# 30_ATMega32u4.net
KiCad netlist of a schematic drawn in Altium Designer
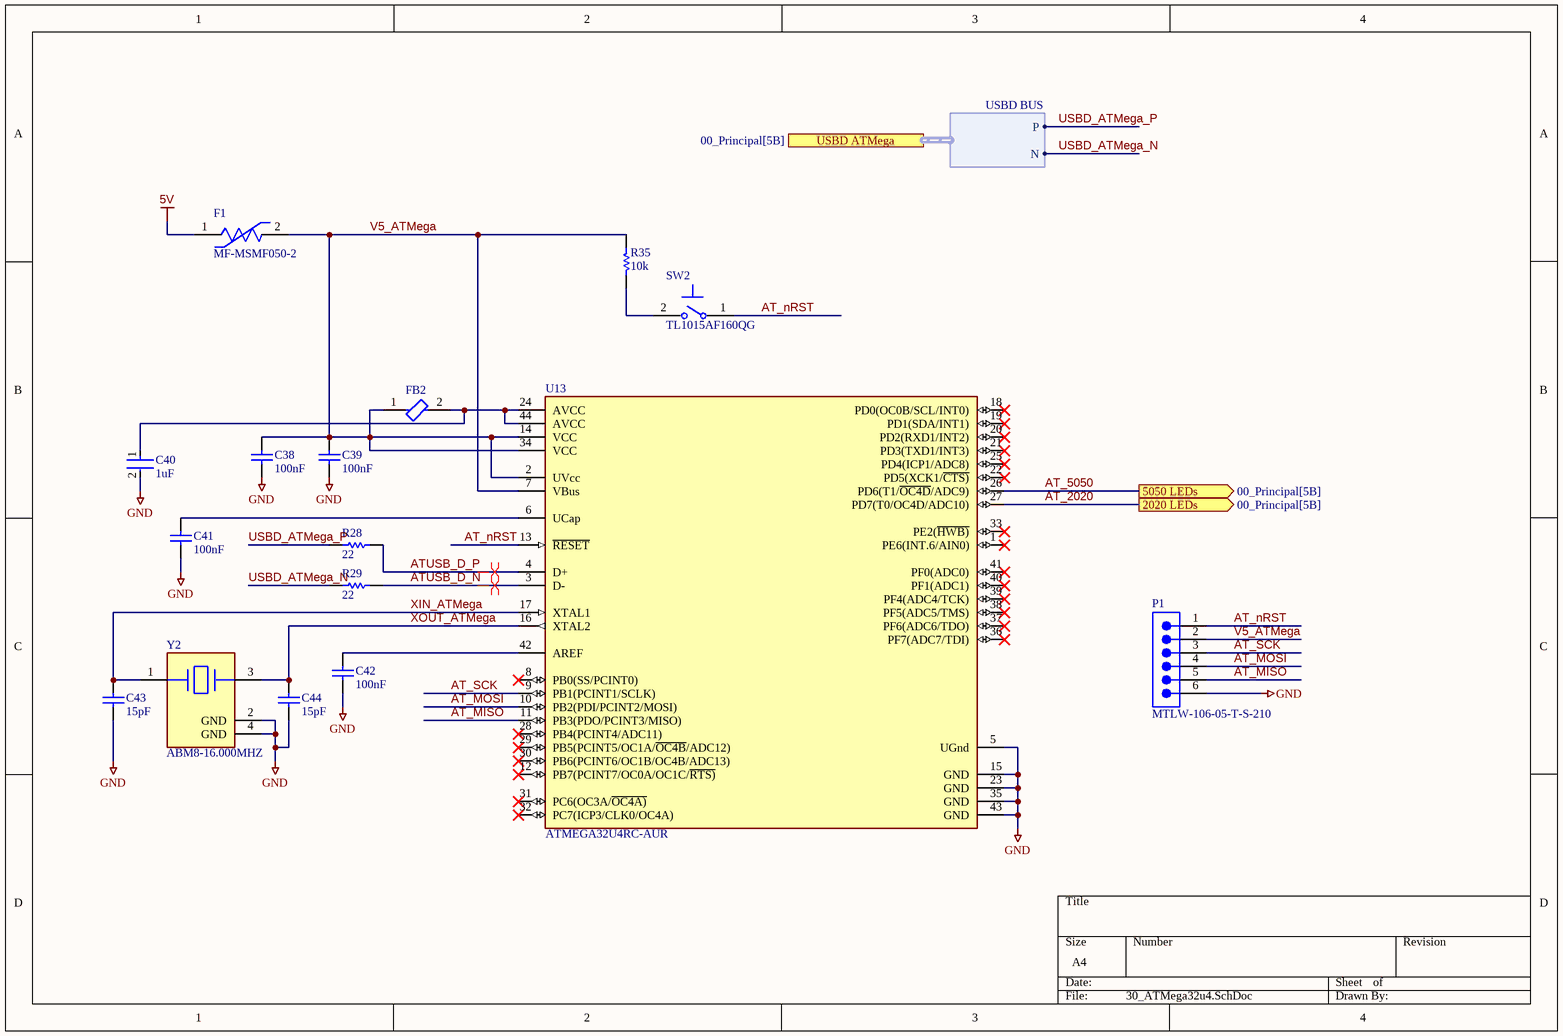
[diagram p0: 30_ATMega32u4.SchDoc]

(export (version "E")
  (design (tool "Eeschema 10.0.6"))
  (components
    (comp (ref "C38")
      (value "100nF")
      (footprint "CAPC1005X55X25NL05T05")
      (fields (field (name "MANUFACTURER") "Vitramon") (field (name "PART NUMBER") "VJ0402Y104KXJCW1BC"))
      (libsource (lib "Altium Content Vault") (part "CAP"))
    )
    (comp (ref "C39")
      (value "100nF")
      (footprint "CAPC1005X55X25NL05T05")
      (fields (field (name "MANUFACTURER") "Vitramon") (field (name "PART NUMBER") "VJ0402Y104KXJCW1BC"))
      (libsource (lib "Altium Content Vault") (part "CAP"))
    )
    (comp (ref "C40")
      (value "1uF")
      (footprint "FP-C0402C-BB-IPC_B")
      (description "CAP CER 1UF 16V X5R 0402")
      (fields (field (name "TOLERANCE") "10%"))
      (libsource (lib "Altium Content Vault") (part "b4654b650e69147ec39a6b967a45e02"))
    )
    (comp (ref "C41")
      (value "100nF")
      (footprint "CAPC1005X55X25NL05T05")
      (fields (field (name "MANUFACTURER") "Vitramon") (field (name "PART NUMBER") "VJ0402Y104KXJCW1BC"))
      (libsource (lib "Altium Content Vault") (part "CAP"))
    )
    (comp (ref "C42")
      (value "100nF")
      (footprint "CAPC1005X55X25NL05T05")
      (fields (field (name "MANUFACTURER") "Vitramon") (field (name "PART NUMBER") "VJ0402Y104KXJCW1BC"))
      (libsource (lib "Altium Content Vault") (part "CAP"))
    )
    (comp (ref "C43")
      (value "15pF")
      (footprint "CAPC1005X56X25NL10T15")
      (fields
        (field (name "MANUFACTURER") "AVX Interconnect / Elco")
        (field (name "PART NUMBER") "0402YA150JAT2A")
      )
      (libsource (lib "Altium Content Vault") (part "CAP"))
    )
    (comp (ref "C44")
      (value "15pF")
      (footprint "CAPC1005X56X25NL10T15")
      (fields
        (field (name "MANUFACTURER") "AVX Interconnect / Elco")
        (field (name "PART NUMBER") "0402YA150JAT2A")
      )
      (libsource (lib "Altium Content Vault") (part "CAP"))
    )
    (comp (ref "F1")
      (value "MF-MSMF050-2")
      (footprint "FP-MF-MSMF050-2-MFG")
      (description "PTC RESET FUSE 15V 500MA 1812")
      (fields
        (field (name "MANUFACTURER") "Bourns")
        (field (name "OCTOPART") "https://octopart.com/mf-msmf050-2-bourns-28047")
      )
      (libsource (lib "Altium Content Vault") (part "fc31388045fc42ab786d6d00b506e9f"))
    )
    (comp (ref "FB2")
      (value "MH2029-300Y")
      (footprint "FP-MH2029-MFG")
      (description "FERRITE BEAD 30 OHM 0805 1LN")
      (fields
        (field (name "OCTOPART") "https://octopart.com/mh2029-300y-bourns-756929")
        (field (name "MANUFACTURER") "Bourns")
      )
      (libsource (lib "Altium Content Vault") (part "5f30dd21d616792df468990f7003faa"))
    )
    (comp (ref "P1")
      (value "MTLW-106-05-T-S-210")
      (footprint "SMTC-MTLW-106-05-X-S-210")
      (fields (field (name "MANUFACTURER") "Samtec"))
      (libsource (lib "Altium Content Vault") (part "SMTC-MTLW-106-05-X-S-210"))
    )
    (comp (ref "R28")
      (value "22")
      (footprint "RESC1005X40X25NL05T05")
      (description "Chip Resistor, 22 Ohm, +/- 1%, 0.1 W, -55 to 155 degC, 0402 (1005 Metric), RoHS, Tape and Reel")
      (fields (field (name "PARTNUMBER") "ERJ-2RKF22R0X") (field (name "TOLERANCE") "1%"))
      (libsource (lib "Altium Content Vault") (part "RES-2"))
    )
    (comp (ref "R29")
      (value "22")
      (footprint "RESC1005X40X25NL05T05")
      (description "Chip Resistor, 22 Ohm, +/- 1%, 0.1 W, -55 to 155 degC, 0402 (1005 Metric), RoHS, Tape and Reel")
      (fields (field (name "PARTNUMBER") "ERJ-2RKF22R0X") (field (name "TOLERANCE") "1%"))
      (libsource (lib "Altium Content Vault") (part "RES-2"))
    )
    (comp (ref "R35")
      (value "10k")
      (footprint "RESC1005X40X25NL05T05")
      (fields (field (name "MANUFACTURER") "Panasonic") (field (name "PART NUMBER") "ERJ-2RHD1002X"))
      (libsource (lib "Altium Content Vault") (part "RES"))
    )
    (comp (ref "SW2")
      (value "TL1015AF160QG")
      (footprint "FP-TL1015AF160QG-MFG")
      (description "SWITCH TACTILE SPST-NO 0.05A 12V")
      (libsource (lib "Altium Content Vault") (part "2041f8efb62e6aaa548c9fd35e2c2f1"))
    )
    (comp (ref "U13")
      (value "ATMEGA32U4RC-AUR")
      (footprint "FP-ML-MFG")
      (description "IC MCU 8BIT 32KB FLASH 44TQFP")
      (libsource (lib "Altium Content Vault") (part "d4543ce5d9f9ec65ed1cf9abf6f4f52"))
    )
    (comp (ref "Y2")
      (value "ABM8-16.000MHZ")
      (footprint "FP-ABM8-MFG")
      (description "Crystal 16MHz ±20ppm 18pF SMD-4 3.2mm x 2.5mm")
      (libsource (lib "Altium Content Vault") (part "dfdb7f9a12507849fb681da9a70121c"))
    )
  )
  (nets
    (net (code "3") (name "/ATUSB_D_N") (class "Default")
      (node (ref "R29") (pin "2") (pinfunction "2_2") (pintype "passive"))
      (node (ref "U13") (pin "3") (pinfunction "D-_3") (pintype "passive"))
    )
    (net (code "4") (name "/ATUSB_D_P") (class "Default")
      (node (ref "R28") (pin "2") (pinfunction "2_2") (pintype "passive"))
      (node (ref "U13") (pin "4") (pinfunction "D+_4") (pintype "passive"))
    )
    (net (code "5") (name "/AT_2020") (class "Default")
      (node (ref "U13") (pin "27") (pinfunction "PD7(T0/OC4D/ADC10)_27") (pintype "bidirectional"))
    )
    (net (code "6") (name "/AT_5050") (class "Default")
      (node (ref "U13") (pin "26") (pinfunction "PD6(T1/~{OC4D}/ADC9)_26") (pintype "bidirectional"))
    )
    (net (code "7") (name "/AT_MISO") (class "Default")
      (node (ref "P1") (pin "5") (pinfunction "5_5") (pintype "passive"))
      (node (ref "U13") (pin "11") (pinfunction "PB3(PDO/PCINT3/MISO)_11") (pintype "bidirectional"))
    )
    (net (code "8") (name "/AT_MOSI") (class "Default")
      (node (ref "P1") (pin "4") (pinfunction "4_4") (pintype "passive"))
      (node (ref "U13") (pin "10") (pinfunction "PB2(PDI/PCINT2/MOSI)_10") (pintype "bidirectional"))
    )
    (net (code "9") (name "/AT_SCK") (class "Default")
      (node (ref "P1") (pin "3") (pinfunction "3_3") (pintype "passive"))
      (node (ref "U13") (pin "9") (pinfunction "PB1(PCINT1/SCLK)_9") (pintype "bidirectional"))
    )
    (net (code "10") (name "/AT_nRST") (class "Default")
      (node (ref "P1") (pin "1") (pinfunction "1_1") (pintype "passive"))
      (node (ref "SW2") (pin "1") (pinfunction "1_1") (pintype "passive"))
      (node (ref "U13") (pin "13") (pinfunction "~{RESET}_13") (pintype "input"))
    )
    (net (code "11") (name "/USBD_ATMega_N") (class "Default")
      (node (ref "R29") (pin "1") (pinfunction "1_1") (pintype "passive"))
    )
    (net (code "12") (name "/USBD_ATMega_P") (class "Default")
      (node (ref "R28") (pin "1") (pinfunction "1_1") (pintype "passive"))
    )
    (net (code "13") (name "/V5_ATMega") (class "Default")
      (node (ref "C38") (pin "2") (pinfunction "2_2") (pintype "passive"))
      (node (ref "C39") (pin "2") (pinfunction "2_2") (pintype "passive"))
      (node (ref "F1") (pin "2") (pinfunction "2_2") (pintype "passive"))
      (node (ref "FB2") (pin "1") (pinfunction "1_1") (pintype "passive"))
      (node (ref "P1") (pin "2") (pinfunction "2_2") (pintype "passive"))
      (node (ref "R35") (pin "2") (pinfunction "2_2") (pintype "passive"))
      (node (ref "U13") (pin "14") (pinfunction "VCC_14") (pintype "power_in"))
      (node (ref "U13") (pin "2") (pinfunction "UVcc_2") (pintype "power_in"))
      (node (ref "U13") (pin "34") (pinfunction "VCC_34") (pintype "power_in"))
      (node (ref "U13") (pin "7") (pinfunction "VBus_7") (pintype "power_in"))
    )
    (net (code "14") (name "/XIN_ATMega") (class "Default")
      (node (ref "C43") (pin "2") (pinfunction "2_2") (pintype "passive"))
      (node (ref "U13") (pin "17") (pinfunction "XTAL1_17") (pintype "input"))
      (node (ref "Y2") (pin "1") (pinfunction "1_1") (pintype "passive"))
    )
    (net (code "15") (name "/XOUT_ATMega") (class "Default")
      (node (ref "C44") (pin "2") (pinfunction "2_2") (pintype "passive"))
      (node (ref "U13") (pin "16") (pinfunction "XTAL2_16") (pintype "output"))
      (node (ref "Y2") (pin "3") (pinfunction "3_3") (pintype "passive"))
    )
    (net (code "17") (name "5V") (class "Default")
      (node (ref "F1") (pin "1") (pinfunction "1_1") (pintype "passive"))
    )
    (net (code "18") (name "GND") (class "Default")
      (node (ref "C38") (pin "1") (pinfunction "1_1") (pintype "passive"))
      (node (ref "C39") (pin "1") (pinfunction "1_1") (pintype "passive"))
      (node (ref "C40") (pin "2") (pinfunction "2_2") (pintype "passive"))
      (node (ref "C41") (pin "1") (pinfunction "1_1") (pintype "passive"))
      (node (ref "C42") (pin "1") (pinfunction "1_1") (pintype "passive"))
      (node (ref "C43") (pin "1") (pinfunction "1_1") (pintype "passive"))
      (node (ref "C44") (pin "1") (pinfunction "1_1") (pintype "passive"))
      (node (ref "P1") (pin "6") (pinfunction "6_6") (pintype "passive"))
      (node (ref "U13") (pin "15") (pinfunction "GND_15") (pintype "power_in"))
      (node (ref "U13") (pin "23") (pinfunction "GND_23") (pintype "power_in"))
      (node (ref "U13") (pin "35") (pinfunction "GND_35") (pintype "power_in"))
      (node (ref "U13") (pin "43") (pinfunction "GND_43") (pintype "power_in"))
      (node (ref "U13") (pin "5") (pinfunction "UGnd_5") (pintype "power_in"))
      (node (ref "Y2") (pin "2") (pinfunction "GND_2") (pintype "power_in"))
      (node (ref "Y2") (pin "4") (pinfunction "GND_4") (pintype "power_in"))
    )
    (net (code "19") (name "Net-(C40-Pad1)") (class "Default")
      (node (ref "C40") (pin "1") (pinfunction "1_1") (pintype "passive"))
      (node (ref "FB2") (pin "2") (pinfunction "2_2") (pintype "passive"))
      (node (ref "U13") (pin "24") (pinfunction "AVCC_24") (pintype "power_in"))
      (node (ref "U13") (pin "44") (pinfunction "AVCC_44") (pintype "power_in"))
    )
    (net (code "20") (name "Net-(R35-Pad1)") (class "Default")
      (node (ref "R35") (pin "1") (pinfunction "1_1") (pintype "passive"))
      (node (ref "SW2") (pin "2") (pinfunction "2_2") (pintype "passive"))
    )
    (net (code "21") (name "Net-(U13-AREF)") (class "Default")
      (node (ref "C42") (pin "2") (pinfunction "2_2") (pintype "passive"))
      (node (ref "U13") (pin "42") (pinfunction "AREF_42") (pintype "passive"))
    )
    (net (code "22") (name "Net-(U13-UCap)") (class "Default")
      (node (ref "C41") (pin "2") (pinfunction "2_2") (pintype "passive"))
      (node (ref "U13") (pin "6") (pinfunction "UCap_6") (pintype "passive"))
    )
    (net (code "23") (name "unconnected-(U13-PB0(SS{slash}PCINT0)-Pad8)") (class "Default")
      (node (ref "U13") (pin "8") (pinfunction "PB0(SS/PCINT0)_8") (pintype "bidirectional+no_connect"))
    )
    (net (code "24") (name "unconnected-(U13-PB4(PCINT4{slash}ADC11)-Pad28)") (class "Default")
      (node (ref "U13") (pin "28") (pinfunction "PB4(PCINT4/ADC11)_28") (pintype "bidirectional+no_connect"))
    )
    (net (code "25") (name "unconnected-(U13-PB5(PCINT5{slash}OC1A{slash}~{OC4B}{slash}ADC12)-Pad29)") (class "Default")
      (node (ref "U13") (pin "29") (pinfunction "PB5(PCINT5/OC1A/~{OC4B}/ADC12)_29") (pintype "bidirectional+no_connect"))
    )
    (net (code "26") (name "unconnected-(U13-PB6(PCINT6{slash}OC1B{slash}OC4B{slash}ADC13)-Pad30)") (class "Default")
      (node (ref "U13") (pin "30") (pinfunction "PB6(PCINT6/OC1B/OC4B/ADC13)_30") (pintype "bidirectional+no_connect"))
    )
    (net (code "27") (name "unconnected-(U13-PB7(PCINT7{slash}OC0A{slash}OC1C{slash}~{RTS)}-Pad12)") (class "Default")
      (node (ref "U13") (pin "12") (pinfunction "PB7(PCINT7/OC0A/OC1C/~{RTS)}_12") (pintype "bidirectional+no_connect"))
    )
    (net (code "28") (name "unconnected-(U13-PC6(OC3A{slash}~{OC4A)}-Pad31)") (class "Default")
      (node (ref "U13") (pin "31") (pinfunction "PC6(OC3A/~{OC4A)}_31") (pintype "bidirectional+no_connect"))
    )
    (net (code "29") (name "unconnected-(U13-PC7(ICP3{slash}CLK0{slash}OC4A)-Pad32)") (class "Default")
      (node (ref "U13") (pin "32") (pinfunction "PC7(ICP3/CLK0/OC4A)_32") (pintype "bidirectional+no_connect"))
    )
    (net (code "30") (name "unconnected-(U13-PD0(OC0B{slash}SCL{slash}INT0)-Pad18)") (class "Default")
      (node (ref "U13") (pin "18") (pinfunction "PD0(OC0B/SCL/INT0)_18") (pintype "bidirectional+no_connect"))
    )
    (net (code "31") (name "unconnected-(U13-PD1(SDA{slash}INT1)-Pad19)") (class "Default")
      (node (ref "U13") (pin "19") (pinfunction "PD1(SDA/INT1)_19") (pintype "bidirectional+no_connect"))
    )
    (net (code "32") (name "unconnected-(U13-PD2(RXD1{slash}INT2)-Pad20)") (class "Default")
      (node (ref "U13") (pin "20") (pinfunction "PD2(RXD1/INT2)_20") (pintype "bidirectional+no_connect"))
    )
    (net (code "33") (name "unconnected-(U13-PD3(TXD1{slash}INT3)-Pad21)") (class "Default")
      (node (ref "U13") (pin "21") (pinfunction "PD3(TXD1/INT3)_21") (pintype "bidirectional+no_connect"))
    )
    (net (code "34") (name "unconnected-(U13-PD4(ICP1{slash}ADC8)-Pad25)") (class "Default")
      (node (ref "U13") (pin "25") (pinfunction "PD4(ICP1/ADC8)_25") (pintype "bidirectional+no_connect"))
    )
    (net (code "35") (name "unconnected-(U13-PD5(XCK1{slash}~{CTS)}-Pad22)") (class "Default")
      (node (ref "U13") (pin "22") (pinfunction "PD5(XCK1/~{CTS)}_22") (pintype "bidirectional+no_connect"))
    )
    (net (code "36") (name "unconnected-(U13-PE2(~{HWB)}-Pad33)") (class "Default")
      (node (ref "U13") (pin "33") (pinfunction "PE2(~{HWB)}_33") (pintype "bidirectional+no_connect"))
    )
    (net (code "37") (name "unconnected-(U13-PE6(INT.6{slash}AIN0)-Pad1)") (class "Default")
      (node (ref "U13") (pin "1") (pinfunction "PE6(INT.6/AIN0)_1") (pintype "bidirectional+no_connect"))
    )
    (net (code "38") (name "unconnected-(U13-PF0(ADC0)-Pad41)") (class "Default")
      (node (ref "U13") (pin "41") (pinfunction "PF0(ADC0)_41") (pintype "bidirectional+no_connect"))
    )
    (net (code "39") (name "unconnected-(U13-PF1(ADC1)-Pad40)") (class "Default")
      (node (ref "U13") (pin "40") (pinfunction "PF1(ADC1)_40") (pintype "bidirectional+no_connect"))
    )
    (net (code "40") (name "unconnected-(U13-PF4(ADC4{slash}TCK)-Pad39)") (class "Default")
      (node (ref "U13") (pin "39") (pinfunction "PF4(ADC4/TCK)_39") (pintype "bidirectional+no_connect"))
    )
    (net (code "41") (name "unconnected-(U13-PF5(ADC5{slash}TMS)-Pad38)") (class "Default")
      (node (ref "U13") (pin "38") (pinfunction "PF5(ADC5/TMS)_38") (pintype "bidirectional+no_connect"))
    )
    (net (code "42") (name "unconnected-(U13-PF6(ADC6{slash}TDO)-Pad37)") (class "Default")
      (node (ref "U13") (pin "37") (pinfunction "PF6(ADC6/TDO)_37") (pintype "bidirectional+no_connect"))
    )
    (net (code "43") (name "unconnected-(U13-PF7(ADC7{slash}TDI)-Pad36)") (class "Default")
      (node (ref "U13") (pin "36") (pinfunction "PF7(ADC7/TDI)_36") (pintype "bidirectional+no_connect"))
    )
  )
)
